# mainboard.net
KiCad netlist of a schematic drawn in EAGLE
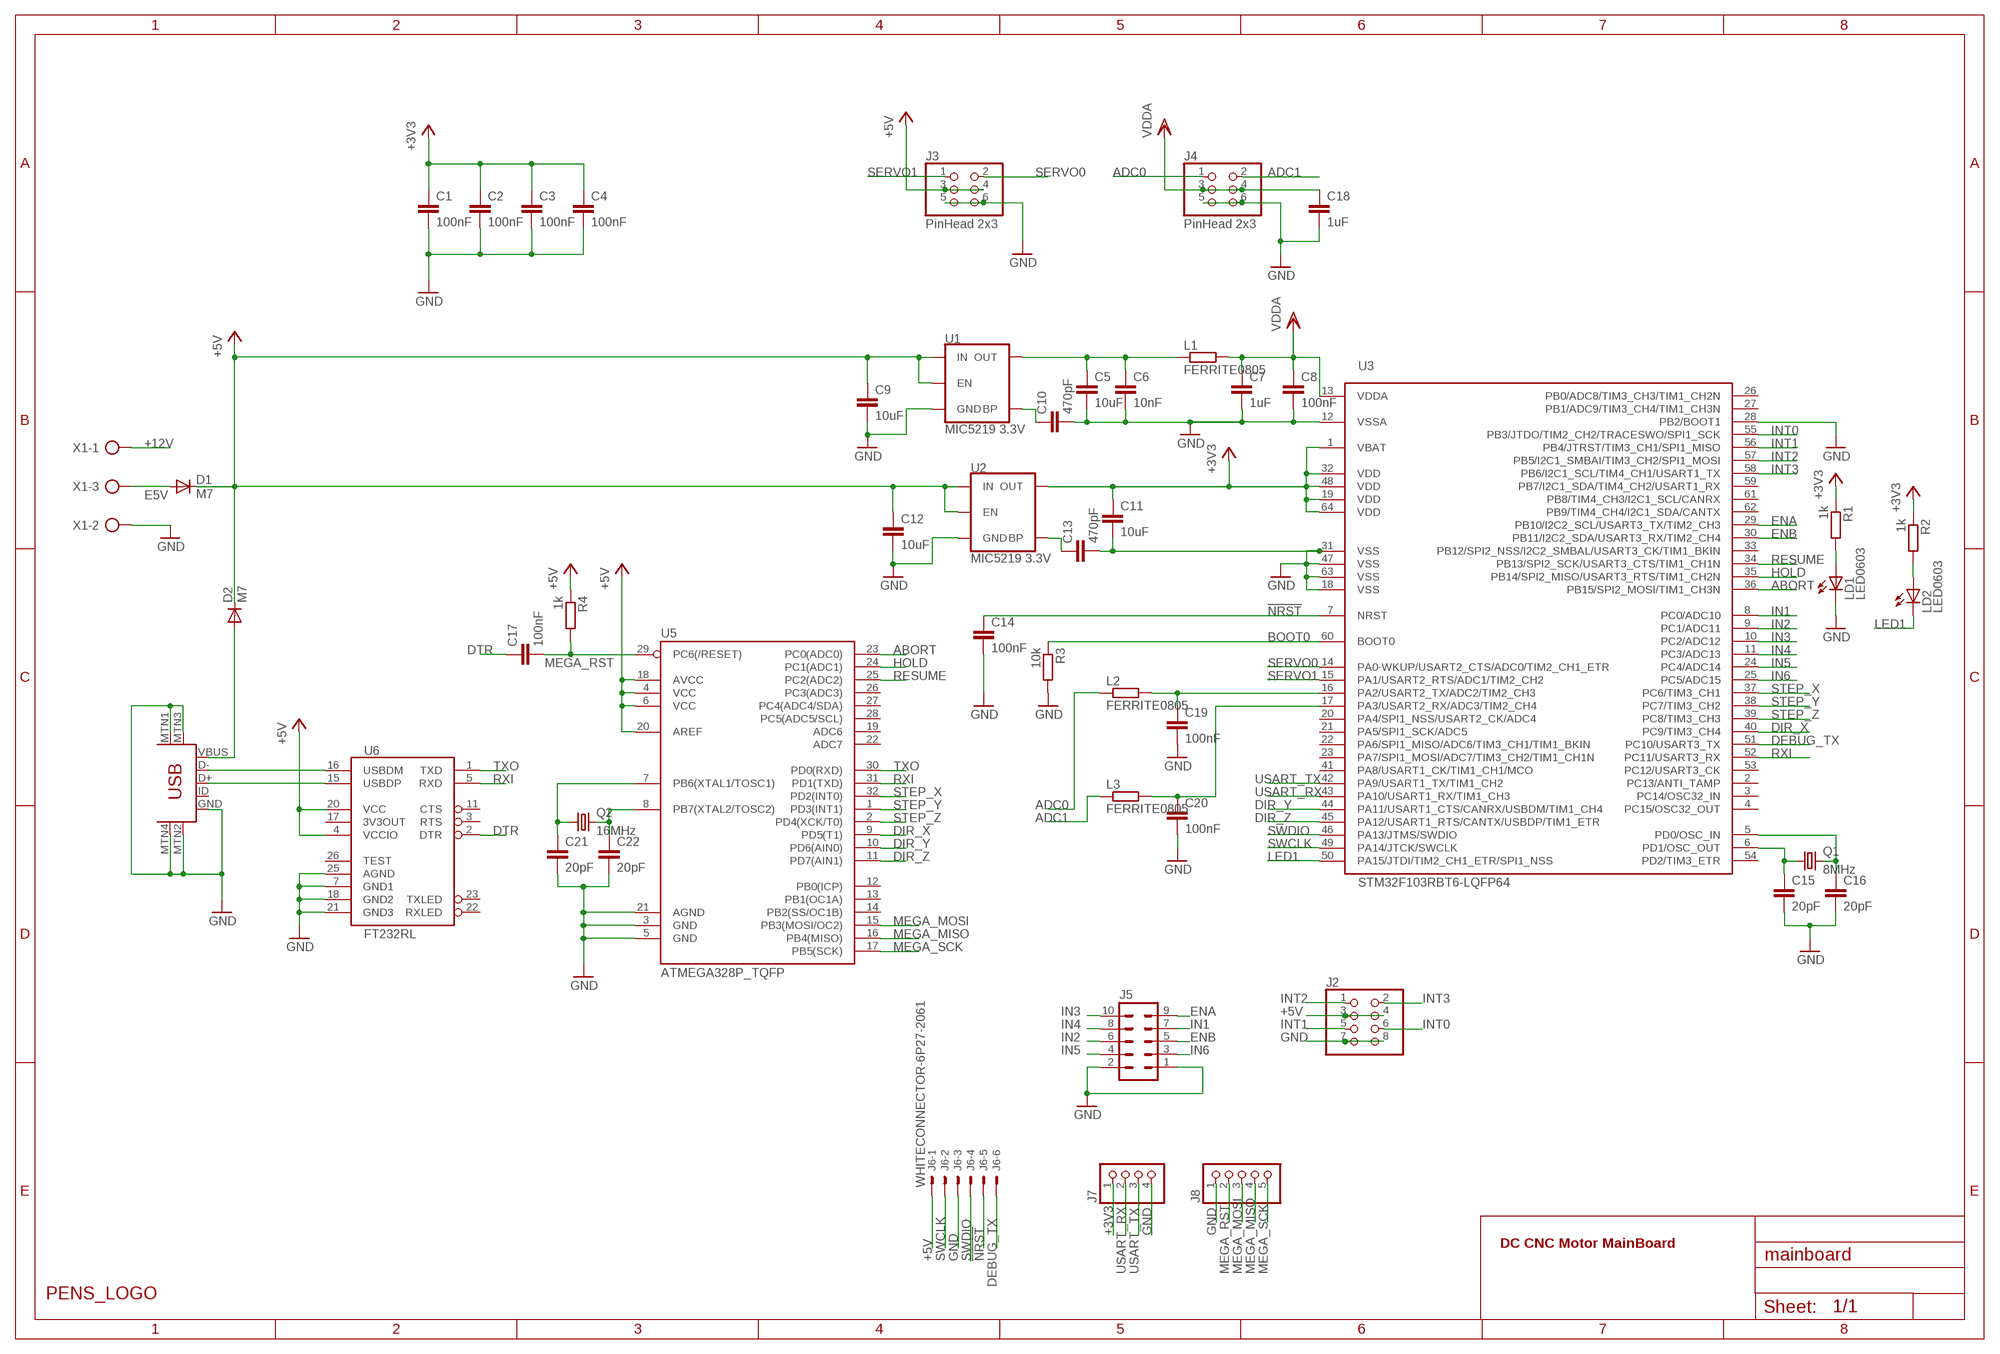
[diagram p0: schematic, sheet 1]

(export (version "E")
  (design (tool "Eeschema 10.0.6"))
  (components
    (comp (ref "C1")
      (value "100nF")
      (footprint "eagle-import:0603_MP")
      (libsource (lib "eagle-import") (part "CAP0603"))
    )
    (comp (ref "C2")
      (value "100nF")
      (footprint "eagle-import:0603_MP")
      (libsource (lib "eagle-import") (part "CAP0603"))
    )
    (comp (ref "C3")
      (value "100nF")
      (footprint "eagle-import:0603_MP")
      (libsource (lib "eagle-import") (part "CAP0603"))
    )
    (comp (ref "C4")
      (value "100nF")
      (footprint "eagle-import:0603_MP")
      (libsource (lib "eagle-import") (part "CAP0603"))
    )
    (comp (ref "C5")
      (value "10uF")
      (footprint "eagle-import:0805_MP")
      (libsource (lib "eagle-import") (part "CAP0805"))
    )
    (comp (ref "C6")
      (value "10nF")
      (footprint "eagle-import:0603_MP")
      (libsource (lib "eagle-import") (part "CAP0603"))
    )
    (comp (ref "C7")
      (value "1uF")
      (footprint "eagle-import:0603_MP")
      (libsource (lib "eagle-import") (part "CAP0603"))
    )
    (comp (ref "C8")
      (value "100nF")
      (footprint "eagle-import:0603_MP")
      (libsource (lib "eagle-import") (part "CAP0603"))
    )
    (comp (ref "C9")
      (value "10uF")
      (footprint "eagle-import:0805_MP")
      (libsource (lib "eagle-import") (part "CAP0805"))
    )
    (comp (ref "C10")
      (value "470pF")
      (footprint "eagle-import:0603_MP")
      (libsource (lib "eagle-import") (part "CAP0603"))
    )
    (comp (ref "C11")
      (value "10uF")
      (footprint "eagle-import:0805_MP")
      (libsource (lib "eagle-import") (part "CAP0805"))
    )
    (comp (ref "C12")
      (value "10uF")
      (footprint "eagle-import:0805_MP")
      (libsource (lib "eagle-import") (part "CAP0805"))
    )
    (comp (ref "C13")
      (value "470pF")
      (footprint "eagle-import:0603_MP")
      (libsource (lib "eagle-import") (part "CAP0603"))
    )
    (comp (ref "C14")
      (value "100nF")
      (footprint "eagle-import:0603_MP")
      (libsource (lib "eagle-import") (part "CAP0603"))
    )
    (comp (ref "C15")
      (value "20pF")
      (footprint "eagle-import:0603_MP")
      (libsource (lib "eagle-import") (part "CAP0603"))
    )
    (comp (ref "C16")
      (value "20pF")
      (footprint "eagle-import:0603_MP")
      (libsource (lib "eagle-import") (part "CAP0603"))
    )
    (comp (ref "C17")
      (value "100nF")
      (footprint "eagle-import:0603_MP")
      (libsource (lib "eagle-import") (part "CAP0603"))
    )
    (comp (ref "C18")
      (value "1uF")
      (footprint "eagle-import:0603_MP")
      (libsource (lib "eagle-import") (part "CAP0603"))
    )
    (comp (ref "C19")
      (value "100nF")
      (footprint "eagle-import:0603_MP")
      (libsource (lib "eagle-import") (part "CAP0603"))
    )
    (comp (ref "C20")
      (value "100nF")
      (footprint "eagle-import:0603_MP")
      (libsource (lib "eagle-import") (part "CAP0603"))
    )
    (comp (ref "C21")
      (value "20pF")
      (footprint "eagle-import:0603_MP")
      (libsource (lib "eagle-import") (part "CAP0603"))
    )
    (comp (ref "C22")
      (value "20pF")
      (footprint "eagle-import:0603_MP")
      (libsource (lib "eagle-import") (part "CAP0603"))
    )
    (comp (ref "D1")
      (value "M7")
      (footprint "eagle-import:DIODE_SMA_ALT")
      (libsource (lib "eagle-import") (part "DIODESMA"))
    )
    (comp (ref "D2")
      (value "M7")
      (footprint "eagle-import:DIODE_SMA_ALT")
      (libsource (lib "eagle-import") (part "DIODESMA"))
    )
    (comp (ref "J1")
      (value "USB-MINI-B-5PIN")
      (footprint "eagle-import:USB-MINIB")
      (libsource (lib "eagle-import") (part "USB-MINI-B-5PIN"))
    )
    (comp (ref "J2")
      (value "PINHD-2X4/90")
      (footprint "eagle-import:2X04_90")
      (libsource (lib "eagle-import") (part "PINHD-2X4/90"))
    )
    (comp (ref "J3")
      (value "PinHead 2x3")
      (footprint "eagle-import:2X03_90")
      (libsource (lib "eagle-import") (part "PINHD-2X3/90"))
    )
    (comp (ref "J4")
      (value "PinHead 2x3")
      (footprint "eagle-import:2X03_90")
      (libsource (lib "eagle-import") (part "PINHD-2X3/90"))
    )
    (comp (ref "J5")
      (value "ML10")
      (footprint "eagle-import:ML10")
      (libsource (lib "eagle-import") (part "ML10"))
    )
    (comp (ref "J6")
      (value "WHITECONNECTOR-6P27-2061")
      (footprint "eagle-import:6410-06")
      (libsource (lib "eagle-import") (part "WHITECONNECTOR-6P27-2061"))
    )
    (comp (ref "J7")
      (value "PINHD-1X4")
      (footprint "eagle-import:1X04")
      (libsource (lib "eagle-import") (part "PINHD-1X4"))
    )
    (comp (ref "J8")
      (value "HEADER-1X51.27MM")
      (footprint "eagle-import:1X05_1.27MM")
      (libsource (lib "eagle-import") (part "HEADER-1X51.27MM"))
    )
    (comp (ref "L1")
      (value "FERRITE0805")
      (footprint "eagle-import:R0805")
      (libsource (lib "eagle-import") (part "FERRITE0805"))
    )
    (comp (ref "L2")
      (value "FERRITE0805")
      (footprint "eagle-import:R0805")
      (libsource (lib "eagle-import") (part "FERRITE0805"))
    )
    (comp (ref "L3")
      (value "FERRITE0805")
      (footprint "eagle-import:R0805")
      (libsource (lib "eagle-import") (part "FERRITE0805"))
    )
    (comp (ref "LD1")
      (value "LED0603")
      (footprint "eagle-import:LED0603")
      (libsource (lib "eagle-import") (part "LED0603"))
    )
    (comp (ref "LD2")
      (value "LED0603")
      (footprint "eagle-import:LED0603")
      (libsource (lib "eagle-import") (part "LED0603"))
    )
    (comp (ref "LOGO1")
      (value "PENS_LOGO")
      (footprint "eagle-import:PENS_LOGO")
      (libsource (lib "eagle-import") (part "PENS_LOGO"))
    )
    (comp (ref "Q1")
      (value "8MHz")
      (footprint "eagle-import:CRYSTAL-DIP")
      (libsource (lib "eagle-import") (part "CRYSTALDIP"))
    )
    (comp (ref "Q2")
      (value "16MHz")
      (footprint "eagle-import:CRYSTAL-DIP")
      (libsource (lib "eagle-import") (part "CRYSTALDIP"))
    )
    (comp (ref "R1")
      (value "1k")
      (footprint "eagle-import:0603_MP")
      (libsource (lib "eagle-import") (part "RESISTOR0603"))
    )
    (comp (ref "R2")
      (value "1k")
      (footprint "eagle-import:0603_MP")
      (libsource (lib "eagle-import") (part "RESISTOR0603"))
    )
    (comp (ref "R3")
      (value "10k")
      (footprint "eagle-import:0603_MP")
      (libsource (lib "eagle-import") (part "RESISTOR0603"))
    )
    (comp (ref "R4")
      (value "1k")
      (footprint "eagle-import:0603_MP")
      (libsource (lib "eagle-import") (part "RESISTOR0603"))
    )
    (comp (ref "U1")
      (value "MIC5219 3.3V")
      (footprint "eagle-import:SOT23-5")
      (libsource (lib "eagle-import") (part "V_REG_MIC52193.3V"))
    )
    (comp (ref "U2")
      (value "MIC5219 3.3V")
      (footprint "eagle-import:SOT23-5")
      (libsource (lib "eagle-import") (part "V_REG_MIC52193.3V"))
    )
    (comp (ref "U3")
      (value "STM32F103RBT6-LQFP64")
      (footprint "eagle-import:LPTQFP64")
      (libsource (lib "eagle-import") (part "STM32F103RBT6-LQFP64"))
    )
    (comp (ref "U5")
      (value "ATMEGA328P_TQFP")
      (footprint "eagle-import:TQFP32-08")
      (libsource (lib "eagle-import") (part "ATMEGA328P_TQFP"))
    )
    (comp (ref "U6")
      (value "FT232RL")
      (footprint "eagle-import:SSOP28DB")
      (libsource (lib "eagle-import") (part "FT232RL-BASICSSOP"))
    )
    (comp (ref "X1")
      (value "AK300/3")
      (footprint "eagle-import:AK300_3")
      (libsource (lib "eagle-import") (part "AK300/3"))
    )
  )
  (nets
    (net (code "1") (name "+3V3") (class "Default")
      (node (ref "C1") (pin "1") (pinfunction "1_1") (pintype "passive"))
      (node (ref "C11") (pin "1") (pinfunction "1_1") (pintype "passive"))
      (node (ref "C2") (pin "1") (pinfunction "1_1") (pintype "passive"))
      (node (ref "C3") (pin "1") (pinfunction "1_1") (pintype "passive"))
      (node (ref "C4") (pin "1") (pinfunction "1_1") (pintype "passive"))
      (node (ref "J7") (pin "1") (pinfunction "1_1") (pintype "passive"))
      (node (ref "R1") (pin "1") (pinfunction "1_1") (pintype "passive"))
      (node (ref "R2") (pin "1") (pinfunction "1_1") (pintype "passive"))
      (node (ref "U2") (pin "5") (pinfunction "OUT_5") (pintype "passive"))
      (node (ref "U3") (pin "1") (pinfunction "VBAT_1") (pintype "power_in"))
      (node (ref "U3") (pin "19") (pinfunction "VDD_19") (pintype "power_in"))
      (node (ref "U3") (pin "32") (pinfunction "VDD_32") (pintype "power_in"))
      (node (ref "U3") (pin "48") (pinfunction "VDD_48") (pintype "power_in"))
      (node (ref "U3") (pin "64") (pinfunction "VDD_64") (pintype "power_in"))
    )
    (net (code "2") (name "+5V") (class "Default")
      (node (ref "C12") (pin "1") (pinfunction "1_1") (pintype "passive"))
      (node (ref "C9") (pin "1") (pinfunction "1_1") (pintype "passive"))
      (node (ref "D1") (pin "C") (pinfunction "C_C") (pintype "passive"))
      (node (ref "D2") (pin "C") (pinfunction "C_C") (pintype "passive"))
      (node (ref "J2") (pin "3") (pinfunction "3_3") (pintype "passive"))
      (node (ref "J2") (pin "4") (pinfunction "4_4") (pintype "passive"))
      (node (ref "J3") (pin "3") (pinfunction "3_3") (pintype "passive"))
      (node (ref "J3") (pin "4") (pinfunction "4_4") (pintype "passive"))
      (node (ref "J6") (pin "1") (pinfunction "S_1") (pintype "passive"))
      (node (ref "R4") (pin "1") (pinfunction "1_1") (pintype "passive"))
      (node (ref "U1") (pin "1") (pinfunction "IN_1") (pintype "input"))
      (node (ref "U1") (pin "3") (pinfunction "EN_3") (pintype "input"))
      (node (ref "U2") (pin "1") (pinfunction "IN_1") (pintype "input"))
      (node (ref "U2") (pin "3") (pinfunction "EN_3") (pintype "input"))
      (node (ref "U5") (pin "18") (pinfunction "AVCC_18") (pintype "bidirectional"))
      (node (ref "U5") (pin "20") (pinfunction "AREF_20") (pintype "bidirectional"))
      (node (ref "U5") (pin "4") (pinfunction "VCC_4") (pintype "bidirectional"))
      (node (ref "U5") (pin "6") (pinfunction "VCC_6") (pintype "bidirectional"))
      (node (ref "U6") (pin "20") (pinfunction "VCC_20") (pintype "power_in"))
      (node (ref "U6") (pin "4") (pinfunction "VCCIO_4") (pintype "power_in"))
    )
    (net (code "3") (name "/+12V") (class "Default")
      (node (ref "X1") (pin "1") (pinfunction "KL_1") (pintype "passive"))
    )
    (net (code "4") (name "/ABORT") (class "Default")
      (node (ref "U3") (pin "36") (pinfunction "PB15/SPI2_MOSI/TIM1_CH3N_36") (pintype "bidirectional"))
      (node (ref "U5") (pin "23") (pinfunction "PC0(ADC0)_23") (pintype "bidirectional"))
    )
    (net (code "5") (name "/ADC0") (class "Default")
      (node (ref "J4") (pin "1") (pinfunction "1_1") (pintype "passive"))
      (node (ref "L2") (pin "1") (pinfunction "1_1") (pintype "passive"))
    )
    (net (code "6") (name "/ADC1") (class "Default")
      (node (ref "J4") (pin "2") (pinfunction "2_2") (pintype "passive"))
      (node (ref "L3") (pin "1") (pinfunction "1_1") (pintype "passive"))
    )
    (net (code "7") (name "/BOOT0") (class "Default")
      (node (ref "R3") (pin "1") (pinfunction "1_1") (pintype "passive"))
      (node (ref "U3") (pin "60") (pinfunction "BOOT0_60") (pintype "input"))
    )
    (net (code "8") (name "/DEBUG_TX") (class "Default")
      (node (ref "J6") (pin "6") (pinfunction "S_6") (pintype "passive"))
      (node (ref "U3") (pin "51") (pinfunction "PC10/USART3_TX_51") (pintype "bidirectional"))
    )
    (net (code "9") (name "/DIR_X") (class "Default")
      (node (ref "U3") (pin "40") (pinfunction "PC9/TIM3_CH4_40") (pintype "bidirectional"))
      (node (ref "U5") (pin "9") (pinfunction "PD5(T1)_9") (pintype "bidirectional"))
    )
    (net (code "10") (name "/DIR_Y") (class "Default")
      (node (ref "U3") (pin "44") (pinfunction "PA11/USART1_CTS/CANRX/USBDM/TIM1_CH4_44") (pintype "bidirectional"))
      (node (ref "U5") (pin "10") (pinfunction "PD6(AIN0)_10") (pintype "bidirectional"))
    )
    (net (code "11") (name "/DIR_Z") (class "Default")
      (node (ref "U3") (pin "45") (pinfunction "PA12/USART1_RTS/CANTX/USBDP/TIM1_ETR_45") (pintype "bidirectional"))
      (node (ref "U5") (pin "11") (pinfunction "PD7(AIN1)_11") (pintype "bidirectional"))
    )
    (net (code "12") (name "/DTR") (class "Default")
      (node (ref "C17") (pin "1") (pinfunction "1_1") (pintype "passive"))
      (node (ref "U6") (pin "2") (pinfunction "DTR_2") (pintype "bidirectional"))
    )
    (net (code "13") (name "/E5V") (class "Default")
      (node (ref "D1") (pin "A") (pinfunction "A_A") (pintype "passive"))
      (node (ref "X1") (pin "3") (pinfunction "KL_3") (pintype "passive"))
    )
    (net (code "14") (name "/ENA") (class "Default")
      (node (ref "J5") (pin "9") (pinfunction "9_9") (pintype "passive"))
      (node (ref "U3") (pin "29") (pinfunction "PB10/I2C2_SCL/USART3_TX/TIM2_CH3_29") (pintype "bidirectional"))
    )
    (net (code "15") (name "/ENB") (class "Default")
      (node (ref "J5") (pin "5") (pinfunction "5_5") (pintype "passive"))
      (node (ref "U3") (pin "30") (pinfunction "PB11/I2C2_SDA/USART3_RX/TIM2_CH4_30") (pintype "bidirectional"))
    )
    (net (code "16") (name "/HOLD") (class "Default")
      (node (ref "U3") (pin "35") (pinfunction "PB14/SPI2_MISO/USART3_RTS/TIM1_CH2N_35") (pintype "bidirectional"))
      (node (ref "U5") (pin "24") (pinfunction "PC1(ADC1)_24") (pintype "bidirectional"))
    )
    (net (code "17") (name "/IN1") (class "Default")
      (node (ref "J5") (pin "7") (pinfunction "7_7") (pintype "passive"))
      (node (ref "U3") (pin "8") (pinfunction "PC0/ADC10_8") (pintype "bidirectional"))
    )
    (net (code "18") (name "/IN2") (class "Default")
      (node (ref "J5") (pin "6") (pinfunction "6_6") (pintype "passive"))
      (node (ref "U3") (pin "9") (pinfunction "PC1/ADC11_9") (pintype "bidirectional"))
    )
    (net (code "19") (name "/IN3") (class "Default")
      (node (ref "J5") (pin "10") (pinfunction "10_10") (pintype "passive"))
      (node (ref "U3") (pin "10") (pinfunction "PC2/ADC12_10") (pintype "bidirectional"))
    )
    (net (code "20") (name "/IN4") (class "Default")
      (node (ref "J5") (pin "8") (pinfunction "8_8") (pintype "passive"))
      (node (ref "U3") (pin "11") (pinfunction "PC3/ADC13_11") (pintype "bidirectional"))
    )
    (net (code "21") (name "/IN5") (class "Default")
      (node (ref "J5") (pin "4") (pinfunction "4_4") (pintype "passive"))
      (node (ref "U3") (pin "24") (pinfunction "PC4/ADC14_24") (pintype "bidirectional"))
    )
    (net (code "22") (name "/IN6") (class "Default")
      (node (ref "J5") (pin "3") (pinfunction "3_3") (pintype "passive"))
      (node (ref "U3") (pin "25") (pinfunction "PC5/ADC15_25") (pintype "bidirectional"))
    )
    (net (code "23") (name "/INT0") (class "Default")
      (node (ref "J2") (pin "6") (pinfunction "6_6") (pintype "passive"))
      (node (ref "U3") (pin "55") (pinfunction "PB3/JTDO/TIM2_CH2/TRACESWO/SPI1_SCK_55") (pintype "bidirectional"))
    )
    (net (code "24") (name "/INT1") (class "Default")
      (node (ref "J2") (pin "5") (pinfunction "5_5") (pintype "passive"))
      (node (ref "U3") (pin "56") (pinfunction "PB4/JTRST/TIM3_CH1/SPI1_MISO_56") (pintype "bidirectional"))
    )
    (net (code "25") (name "/INT2") (class "Default")
      (node (ref "J2") (pin "1") (pinfunction "1_1") (pintype "passive"))
      (node (ref "U3") (pin "57") (pinfunction "PB5/I2C1_SMBAI/TIM3_CH2/SPI1_MOSI_57") (pintype "bidirectional"))
    )
    (net (code "26") (name "/INT3") (class "Default")
      (node (ref "J2") (pin "2") (pinfunction "2_2") (pintype "passive"))
      (node (ref "U3") (pin "58") (pinfunction "PB6/I2C1_SCL/TIM4_CH1/USART1_TX_58") (pintype "bidirectional"))
    )
    (net (code "27") (name "/LED1") (class "Default")
      (node (ref "LD2") (pin "C") (pinfunction "C_C") (pintype "passive"))
      (node (ref "U3") (pin "50") (pinfunction "PA15/JTDI/TIM2_CH1_ETR/SPI1_NSS_50") (pintype "bidirectional"))
    )
    (net (code "28") (name "/MEGA_MISO") (class "Default")
      (node (ref "J8") (pin "4") (pinfunction "4_4") (pintype "passive"))
      (node (ref "U5") (pin "16") (pinfunction "PB4(MISO)_16") (pintype "bidirectional"))
    )
    (net (code "29") (name "/MEGA_MOSI") (class "Default")
      (node (ref "J8") (pin "3") (pinfunction "3_3") (pintype "passive"))
      (node (ref "U5") (pin "15") (pinfunction "PB3(MOSI/OC2)_15") (pintype "bidirectional"))
    )
    (net (code "30") (name "/MEGA_RST") (class "Default")
      (node (ref "C17") (pin "2") (pinfunction "2_2") (pintype "passive"))
      (node (ref "J8") (pin "2") (pinfunction "2_2") (pintype "passive"))
      (node (ref "R4") (pin "2") (pinfunction "2_2") (pintype "passive"))
      (node (ref "U5") (pin "29") (pinfunction "PC6(/RESET)_29") (pintype "bidirectional"))
    )
    (net (code "31") (name "/MEGA_SCK") (class "Default")
      (node (ref "J8") (pin "5") (pinfunction "5_5") (pintype "passive"))
      (node (ref "U5") (pin "17") (pinfunction "PB5(SCK)_17") (pintype "bidirectional"))
    )
    (net (code "32") (name "/RESUME") (class "Default")
      (node (ref "U3") (pin "34") (pinfunction "PB13/SPI2_SCK/USART3_CTS/TIM1_CH1N_34") (pintype "bidirectional"))
      (node (ref "U5") (pin "25") (pinfunction "PC2(ADC2)_25") (pintype "bidirectional"))
    )
    (net (code "33") (name "/RXI") (class "Default")
      (node (ref "U3") (pin "52") (pinfunction "PC11/USART3_RX_52") (pintype "bidirectional"))
      (node (ref "U5") (pin "31") (pinfunction "PD1(TXD)_31") (pintype "bidirectional"))
      (node (ref "U6") (pin "5") (pinfunction "RXD_5") (pintype "input"))
    )
    (net (code "34") (name "/SERVO0") (class "Default")
      (node (ref "J3") (pin "2") (pinfunction "2_2") (pintype "passive"))
      (node (ref "U3") (pin "14") (pinfunction "PA0-WKUP/USART2_CTS/ADC0/TIM2_CH1_ETR_14") (pintype "bidirectional"))
    )
    (net (code "35") (name "/SERVO1") (class "Default")
      (node (ref "J3") (pin "1") (pinfunction "1_1") (pintype "passive"))
      (node (ref "U3") (pin "15") (pinfunction "PA1/USART2_RTS/ADC1/TIM2_CH2_15") (pintype "bidirectional"))
    )
    (net (code "36") (name "/STEP_X") (class "Default")
      (node (ref "U3") (pin "37") (pinfunction "PC6/TIM3_CH1_37") (pintype "bidirectional"))
      (node (ref "U5") (pin "32") (pinfunction "PD2(INT0)_32") (pintype "bidirectional"))
    )
    (net (code "37") (name "/STEP_Y") (class "Default")
      (node (ref "U3") (pin "38") (pinfunction "PC7/TIM3_CH2_38") (pintype "bidirectional"))
      (node (ref "U5") (pin "1") (pinfunction "PD3(INT1)_1") (pintype "bidirectional"))
    )
    (net (code "38") (name "/STEP_Z") (class "Default")
      (node (ref "U3") (pin "39") (pinfunction "PC8/TIM3_CH3_39") (pintype "bidirectional"))
      (node (ref "U5") (pin "2") (pinfunction "PD4(XCK/T0)_2") (pintype "bidirectional"))
    )
    (net (code "39") (name "/SWCLK") (class "Default")
      (node (ref "J6") (pin "2") (pinfunction "S_2") (pintype "passive"))
      (node (ref "U3") (pin "49") (pinfunction "PA14/JTCK/SWCLK_49") (pintype "bidirectional"))
    )
    (net (code "40") (name "/SWDIO") (class "Default")
      (node (ref "J6") (pin "4") (pinfunction "S_4") (pintype "passive"))
      (node (ref "U3") (pin "46") (pinfunction "PA13/JTMS/SWDIO_46") (pintype "bidirectional"))
    )
    (net (code "41") (name "/TXO") (class "Default")
      (node (ref "U5") (pin "30") (pinfunction "PD0(RXD)_30") (pintype "bidirectional"))
      (node (ref "U6") (pin "1") (pinfunction "TXD_1") (pintype "output"))
    )
    (net (code "42") (name "/USART_RX") (class "Default")
      (node (ref "J7") (pin "2") (pinfunction "2_2") (pintype "passive"))
      (node (ref "U3") (pin "43") (pinfunction "PA10/USART1_RX/TIM1_CH3_43") (pintype "bidirectional"))
    )
    (net (code "43") (name "/USART_TX") (class "Default")
      (node (ref "J7") (pin "3") (pinfunction "3_3") (pintype "passive"))
      (node (ref "U3") (pin "42") (pinfunction "PA9/USART1_TX/TIM1_CH2_42") (pintype "bidirectional"))
    )
    (net (code "44") (name "/~{NRST}") (class "Default")
      (node (ref "C14") (pin "1") (pinfunction "1_1") (pintype "passive"))
      (node (ref "J6") (pin "5") (pinfunction "S_5") (pintype "passive"))
      (node (ref "U3") (pin "7") (pinfunction "NRST_7") (pintype "input"))
    )
    (net (code "45") (name "GND") (class "Default")
      (node (ref "C1") (pin "2") (pinfunction "2_2") (pintype "passive"))
      (node (ref "C10") (pin "2") (pinfunction "2_2") (pintype "passive"))
      (node (ref "C11") (pin "2") (pinfunction "2_2") (pintype "passive"))
      (node (ref "C12") (pin "2") (pinfunction "2_2") (pintype "passive"))
      (node (ref "C13") (pin "2") (pinfunction "2_2") (pintype "passive"))
      (node (ref "C14") (pin "2") (pinfunction "2_2") (pintype "passive"))
      (node (ref "C15") (pin "2") (pinfunction "2_2") (pintype "passive"))
      (node (ref "C16") (pin "2") (pinfunction "2_2") (pintype "passive"))
      (node (ref "C18") (pin "2") (pinfunction "2_2") (pintype "passive"))
      (node (ref "C19") (pin "2") (pinfunction "2_2") (pintype "passive"))
      (node (ref "C2") (pin "2") (pinfunction "2_2") (pintype "passive"))
      (node (ref "C20") (pin "2") (pinfunction "2_2") (pintype "passive"))
      (node (ref "C21") (pin "2") (pinfunction "2_2") (pintype "passive"))
      (node (ref "C22") (pin "2") (pinfunction "2_2") (pintype "passive"))
      (node (ref "C3") (pin "2") (pinfunction "2_2") (pintype "passive"))
      (node (ref "C4") (pin "2") (pinfunction "2_2") (pintype "passive"))
      (node (ref "C5") (pin "2") (pinfunction "2_2") (pintype "passive"))
      (node (ref "C6") (pin "2") (pinfunction "2_2") (pintype "passive"))
      (node (ref "C7") (pin "2") (pinfunction "2_2") (pintype "passive"))
      (node (ref "C8") (pin "2") (pinfunction "2_2") (pintype "passive"))
      (node (ref "C9") (pin "2") (pinfunction "2_2") (pintype "passive"))
      (node (ref "J1") (pin "GND") (pinfunction "GND_GND") (pintype "bidirectional"))
      (node (ref "J1") (pin "MTN1") (pinfunction "MTN2_MTN1") (pintype "bidirectional"))
      (node (ref "J1") (pin "MTN2") (pinfunction "MTN3_MTN2") (pintype "bidirectional"))
      (node (ref "J1") (pin "MTN3") (pinfunction "MTN1_MTN3") (pintype "bidirectional"))
      (node (ref "J1") (pin "MTN4") (pinfunction "MTN4_MTN4") (pintype "bidirectional"))
      (node (ref "J2") (pin "7") (pinfunction "7_7") (pintype "passive"))
      (node (ref "J2") (pin "8") (pinfunction "8_8") (pintype "passive"))
      (node (ref "J3") (pin "5") (pinfunction "5_5") (pintype "passive"))
      (node (ref "J3") (pin "6") (pinfunction "6_6") (pintype "passive"))
      (node (ref "J4") (pin "5") (pinfunction "5_5") (pintype "passive"))
      (node (ref "J4") (pin "6") (pinfunction "6_6") (pintype "passive"))
      (node (ref "J5") (pin "1") (pinfunction "1_1") (pintype "passive"))
      (node (ref "J5") (pin "2") (pinfunction "2_2") (pintype "passive"))
      (node (ref "J6") (pin "3") (pinfunction "S_3") (pintype "passive"))
      (node (ref "J7") (pin "4") (pinfunction "4_4") (pintype "passive"))
      (node (ref "J8") (pin "1") (pinfunction "1_1") (pintype "passive"))
      (node (ref "LD1") (pin "C") (pinfunction "C_C") (pintype "passive"))
      (node (ref "R3") (pin "2") (pinfunction "2_2") (pintype "passive"))
      (node (ref "U1") (pin "2") (pinfunction "GND_2") (pintype "input"))
      (node (ref "U2") (pin "2") (pinfunction "GND_2") (pintype "input"))
      (node (ref "U3") (pin "12") (pinfunction "VSSA_12") (pintype "power_in"))
      (node (ref "U3") (pin "18") (pinfunction "VSS_18") (pintype "power_in"))
      (node (ref "U3") (pin "28") (pinfunction "PB2/BOOT1_28") (pintype "bidirectional"))
      (node (ref "U3") (pin "31") (pinfunction "VSS_31") (pintype "power_in"))
      (node (ref "U3") (pin "47") (pinfunction "VSS_47") (pintype "power_in"))
      (node (ref "U3") (pin "63") (pinfunction "VSS_63") (pintype "power_in"))
      (node (ref "U5") (pin "21") (pinfunction "AGND_21") (pintype "bidirectional"))
      (node (ref "U5") (pin "3") (pinfunction "GND_3") (pintype "bidirectional"))
      (node (ref "U5") (pin "5") (pinfunction "GND_5") (pintype "bidirectional"))
      (node (ref "U6") (pin "18") (pinfunction "GND2_18") (pintype "power_in"))
      (node (ref "U6") (pin "21") (pinfunction "GND3_21") (pintype "power_in"))
      (node (ref "U6") (pin "25") (pinfunction "AGND_25") (pintype "power_in"))
      (node (ref "U6") (pin "7") (pinfunction "GND1_7") (pintype "power_in"))
      (node (ref "X1") (pin "2") (pinfunction "KL_2") (pintype "passive"))
    )
    (net (code "46") (name "Net-(D2-PadA)") (class "Default")
      (node (ref "D2") (pin "A") (pinfunction "A_A") (pintype "passive"))
      (node (ref "J1") (pin "VBUS") (pinfunction "VBUS_VBUS") (pintype "bidirectional"))
    )
    (net (code "47") (name "Net-(LD1-PadA)") (class "Default")
      (node (ref "LD1") (pin "A") (pinfunction "A_A") (pintype "passive"))
      (node (ref "R1") (pin "2") (pinfunction "2_2") (pintype "passive"))
    )
    (net (code "48") (name "Net-(LD2-PadA)") (class "Default")
      (node (ref "LD2") (pin "A") (pinfunction "A_A") (pintype "passive"))
      (node (ref "R2") (pin "2") (pinfunction "2_2") (pintype "passive"))
    )
    (net (code "49") (name "Net-(U1-BP)") (class "Default")
      (node (ref "C10") (pin "1") (pinfunction "1_1") (pintype "passive"))
      (node (ref "U1") (pin "4") (pinfunction "BP_4") (pintype "input"))
    )
    (net (code "50") (name "Net-(U1-OUT)") (class "Default")
      (node (ref "C5") (pin "1") (pinfunction "1_1") (pintype "passive"))
      (node (ref "C6") (pin "1") (pinfunction "1_1") (pintype "passive"))
      (node (ref "L1") (pin "1") (pinfunction "1_1") (pintype "passive"))
      (node (ref "U1") (pin "5") (pinfunction "OUT_5") (pintype "passive"))
    )
    (net (code "51") (name "Net-(U2-BP)") (class "Default")
      (node (ref "C13") (pin "1") (pinfunction "1_1") (pintype "passive"))
      (node (ref "U2") (pin "4") (pinfunction "BP_4") (pintype "input"))
    )
    (net (code "52") (name "Net-(U3-PA2{slash}USART2_TX{slash}ADC2{slash}TIM2_CH3)") (class "Default")
      (node (ref "C19") (pin "1") (pinfunction "1_1") (pintype "passive"))
      (node (ref "L2") (pin "2") (pinfunction "2_2") (pintype "passive"))
      (node (ref "U3") (pin "16") (pinfunction "PA2/USART2_TX/ADC2/TIM2_CH3_16") (pintype "bidirectional"))
    )
    (net (code "53") (name "Net-(U3-PA3{slash}USART2_RX{slash}ADC3{slash}TIM2_CH4)") (class "Default")
      (node (ref "C20") (pin "1") (pinfunction "1_1") (pintype "passive"))
      (node (ref "L3") (pin "2") (pinfunction "2_2") (pintype "passive"))
      (node (ref "U3") (pin "17") (pinfunction "PA3/USART2_RX/ADC3/TIM2_CH4_17") (pintype "bidirectional"))
    )
    (net (code "54") (name "Net-(U3-PD0{slash}OSC_IN)") (class "Default")
      (node (ref "C16") (pin "1") (pinfunction "1_1") (pintype "passive"))
      (node (ref "Q1") (pin "2") (pinfunction "2_2") (pintype "passive"))
      (node (ref "U3") (pin "5") (pinfunction "PD0/OSC_IN_5") (pintype "bidirectional"))
    )
    (net (code "55") (name "Net-(U3-PD1{slash}OSC_OUT)") (class "Default")
      (node (ref "C15") (pin "1") (pinfunction "1_1") (pintype "passive"))
      (node (ref "Q1") (pin "1") (pinfunction "1_1") (pintype "passive"))
      (node (ref "U3") (pin "6") (pinfunction "PD1/OSC_OUT_6") (pintype "bidirectional"))
    )
    (net (code "56") (name "Net-(U5-PB6(XTAL1{slash}TOSC1))") (class "Default")
      (node (ref "C21") (pin "1") (pinfunction "1_1") (pintype "passive"))
      (node (ref "Q2") (pin "1") (pinfunction "1_1") (pintype "passive"))
      (node (ref "U5") (pin "7") (pinfunction "PB6(XTAL1/TOSC1)_7") (pintype "bidirectional"))
    )
    (net (code "57") (name "Net-(U5-PB7(XTAL2{slash}TOSC2))") (class "Default")
      (node (ref "C22") (pin "1") (pinfunction "1_1") (pintype "passive"))
      (node (ref "Q2") (pin "2") (pinfunction "2_2") (pintype "passive"))
      (node (ref "U5") (pin "8") (pinfunction "PB7(XTAL2/TOSC2)_8") (pintype "bidirectional"))
    )
    (net (code "58") (name "Net-(U6-USBDM)") (class "Default")
      (node (ref "J1") (pin "D-") (pinfunction "D-_D-") (pintype "bidirectional"))
      (node (ref "U6") (pin "16") (pinfunction "USBDM_16") (pintype "bidirectional"))
    )
    (net (code "59") (name "Net-(U6-USBDP)") (class "Default")
      (node (ref "J1") (pin "D+") (pinfunction "D+_D+") (pintype "bidirectional"))
      (node (ref "U6") (pin "15") (pinfunction "USBDP_15") (pintype "bidirectional"))
    )
    (net (code "60") (name "VDDA") (class "Default")
      (node (ref "C18") (pin "1") (pinfunction "1_1") (pintype "passive"))
      (node (ref "C7") (pin "1") (pinfunction "1_1") (pintype "passive"))
      (node (ref "C8") (pin "1") (pinfunction "1_1") (pintype "passive"))
      (node (ref "J4") (pin "3") (pinfunction "3_3") (pintype "passive"))
      (node (ref "J4") (pin "4") (pinfunction "4_4") (pintype "passive"))
      (node (ref "L1") (pin "2") (pinfunction "2_2") (pintype "passive"))
      (node (ref "U3") (pin "13") (pinfunction "VDDA_13") (pintype "power_in"))
    )
    (net (code "61") (name "unconnected-(J1-PadID)") (class "Default")
      (node (ref "J1") (pin "ID") (pinfunction "ID_ID") (pintype "bidirectional"))
    )
    (net (code "62") (name "unconnected-(U3-PA4{slash}SPI1_NSS{slash}USART2_CK{slash}ADC4-Pad20)") (class "Default")
      (node (ref "U3") (pin "20") (pinfunction "PA4/SPI1_NSS/USART2_CK/ADC4_20") (pintype "bidirectional"))
    )
    (net (code "63") (name "unconnected-(U3-PA5{slash}SPI1_SCK{slash}ADC5-Pad21)") (class "Default")
      (node (ref "U3") (pin "21") (pinfunction "PA5/SPI1_SCK/ADC5_21") (pintype "bidirectional"))
    )
    (net (code "64") (name "unconnected-(U3-PA6{slash}SPI1_MISO{slash}ADC6{slash}TIM3_CH1{slash}TIM1_BKIN-Pad22)") (class "Default")
      (node (ref "U3") (pin "22") (pinfunction "PA6/SPI1_MISO/ADC6/TIM3_CH1/TIM1_BKIN_22") (pintype "bidirectional"))
    )
    (net (code "65") (name "unconnected-(U3-PA7{slash}SPI1_MOSI{slash}ADC7{slash}TIM3_CH2{slash}TIM1_CH1N-Pad23)") (class "Default")
      (node (ref "U3") (pin "23") (pinfunction "PA7/SPI1_MOSI/ADC7/TIM3_CH2/TIM1_CH1N_23") (pintype "bidirectional"))
    )
    (net (code "66") (name "unconnected-(U3-PA8{slash}USART1_CK{slash}TIM1_CH1{slash}MCO-Pad41)") (class "Default")
      (node (ref "U3") (pin "41") (pinfunction "PA8/USART1_CK/TIM1_CH1/MCO_41") (pintype "bidirectional"))
    )
    (net (code "67") (name "unconnected-(U3-PB0{slash}ADC8{slash}TIM3_CH3{slash}TIM1_CH2N-Pad26)") (class "Default")
      (node (ref "U3") (pin "26") (pinfunction "PB0/ADC8/TIM3_CH3/TIM1_CH2N_26") (pintype "bidirectional"))
    )
    (net (code "68") (name "unconnected-(U3-PB1{slash}ADC9{slash}TIM3_CH4{slash}TIM1_CH3N-Pad27)") (class "Default")
      (node (ref "U3") (pin "27") (pinfunction "PB1/ADC9/TIM3_CH4/TIM1_CH3N_27") (pintype "bidirectional"))
    )
    (net (code "69") (name "unconnected-(U3-PB7{slash}I2C1_SDA{slash}TIM4_CH2{slash}USART1_RX-Pad59)") (class "Default")
      (node (ref "U3") (pin "59") (pinfunction "PB7/I2C1_SDA/TIM4_CH2/USART1_RX_59") (pintype "bidirectional"))
    )
    (net (code "70") (name "unconnected-(U3-PB8{slash}TIM4_CH3{slash}I2C1_SCL{slash}CANRX-Pad61)") (class "Default")
      (node (ref "U3") (pin "61") (pinfunction "PB8/TIM4_CH3/I2C1_SCL/CANRX_61") (pintype "bidirectional"))
    )
    (net (code "71") (name "unconnected-(U3-PB9{slash}TIM4_CH4{slash}I2C1_SDA{slash}CANTX-Pad62)") (class "Default")
      (node (ref "U3") (pin "62") (pinfunction "PB9/TIM4_CH4/I2C1_SDA/CANTX_62") (pintype "bidirectional"))
    )
    (net (code "72") (name "unconnected-(U3-PB12{slash}SPI2_NSS{slash}I2C2_SMBAL{slash}USART3_CK{slash}TIM1_BKIN-Pad33)") (class "Default")
      (node (ref "U3") (pin "33") (pinfunction "PB12/SPI2_NSS/I2C2_SMBAL/USART3_CK/TIM1_BKIN_33") (pintype "bidirectional"))
    )
    (net (code "73") (name "unconnected-(U3-PC12{slash}USART3_CK-Pad53)") (class "Default")
      (node (ref "U3") (pin "53") (pinfunction "PC12/USART3_CK_53") (pintype "bidirectional"))
    )
    (net (code "74") (name "unconnected-(U3-PC13{slash}ANTI_TAMP-Pad2)") (class "Default")
      (node (ref "U3") (pin "2") (pinfunction "PC13/ANTI_TAMP_2") (pintype "bidirectional"))
    )
    (net (code "75") (name "unconnected-(U3-PC14{slash}OSC32_IN-Pad3)") (class "Default")
      (node (ref "U3") (pin "3") (pinfunction "PC14/OSC32_IN_3") (pintype "bidirectional"))
    )
    (net (code "76") (name "unconnected-(U3-PC15{slash}OSC32_OUT-Pad4)") (class "Default")
      (node (ref "U3") (pin "4") (pinfunction "PC15/OSC32_OUT_4") (pintype "bidirectional"))
    )
    (net (code "77") (name "unconnected-(U3-PD2{slash}TIM3_ETR-Pad54)") (class "Default")
      (node (ref "U3") (pin "54") (pinfunction "PD2/TIM3_ETR_54") (pintype "bidirectional"))
    )
    (net (code "78") (name "unconnected-(U5-ADC6-Pad19)") (class "Default")
      (node (ref "U5") (pin "19") (pinfunction "ADC6_19") (pintype "bidirectional"))
    )
    (net (code "79") (name "unconnected-(U5-ADC7-Pad22)") (class "Default")
      (node (ref "U5") (pin "22") (pinfunction "ADC7_22") (pintype "bidirectional"))
    )
    (net (code "80") (name "unconnected-(U5-PB0(ICP)-Pad12)") (class "Default")
      (node (ref "U5") (pin "12") (pinfunction "PB0(ICP)_12") (pintype "bidirectional"))
    )
    (net (code "81") (name "unconnected-(U5-PB1(OC1A)-Pad13)") (class "Default")
      (node (ref "U5") (pin "13") (pinfunction "PB1(OC1A)_13") (pintype "bidirectional"))
    )
    (net (code "82") (name "unconnected-(U5-PB2(SS{slash}OC1B)-Pad14)") (class "Default")
      (node (ref "U5") (pin "14") (pinfunction "PB2(SS/OC1B)_14") (pintype "bidirectional"))
    )
    (net (code "83") (name "unconnected-(U5-PC3(ADC3)-Pad26)") (class "Default")
      (node (ref "U5") (pin "26") (pinfunction "PC3(ADC3)_26") (pintype "bidirectional"))
    )
    (net (code "84") (name "unconnected-(U5-PC4(ADC4{slash}SDA)-Pad27)") (class "Default")
      (node (ref "U5") (pin "27") (pinfunction "PC4(ADC4/SDA)_27") (pintype "bidirectional"))
    )
    (net (code "85") (name "unconnected-(U5-PC5(ADC5{slash}SCL)-Pad28)") (class "Default")
      (node (ref "U5") (pin "28") (pinfunction "PC5(ADC5/SCL)_28") (pintype "bidirectional"))
    )
    (net (code "86") (name "unconnected-(U6-3V3OUT-Pad17)") (class "Default")
      (node (ref "U6") (pin "17") (pinfunction "3V3OUT_17") (pintype "output"))
    )
    (net (code "87") (name "unconnected-(U6-CTS-Pad11)") (class "Default")
      (node (ref "U6") (pin "11") (pinfunction "CTS_11") (pintype "bidirectional"))
    )
    (net (code "88") (name "unconnected-(U6-RTS-Pad3)") (class "Default")
      (node (ref "U6") (pin "3") (pinfunction "RTS_3") (pintype "bidirectional"))
    )
    (net (code "89") (name "unconnected-(U6-RXLED-Pad22)") (class "Default")
      (node (ref "U6") (pin "22") (pinfunction "RXLED_22") (pintype "bidirectional"))
    )
    (net (code "90") (name "unconnected-(U6-TEST-Pad26)") (class "Default")
      (node (ref "U6") (pin "26") (pinfunction "TEST_26") (pintype "input"))
    )
    (net (code "91") (name "unconnected-(U6-TXLED-Pad23)") (class "Default")
      (node (ref "U6") (pin "23") (pinfunction "TXLED_23") (pintype "bidirectional"))
    )
  )
)
